# STM32F103RC.net
KiCad netlist of a schematic drawn in Altium Designer
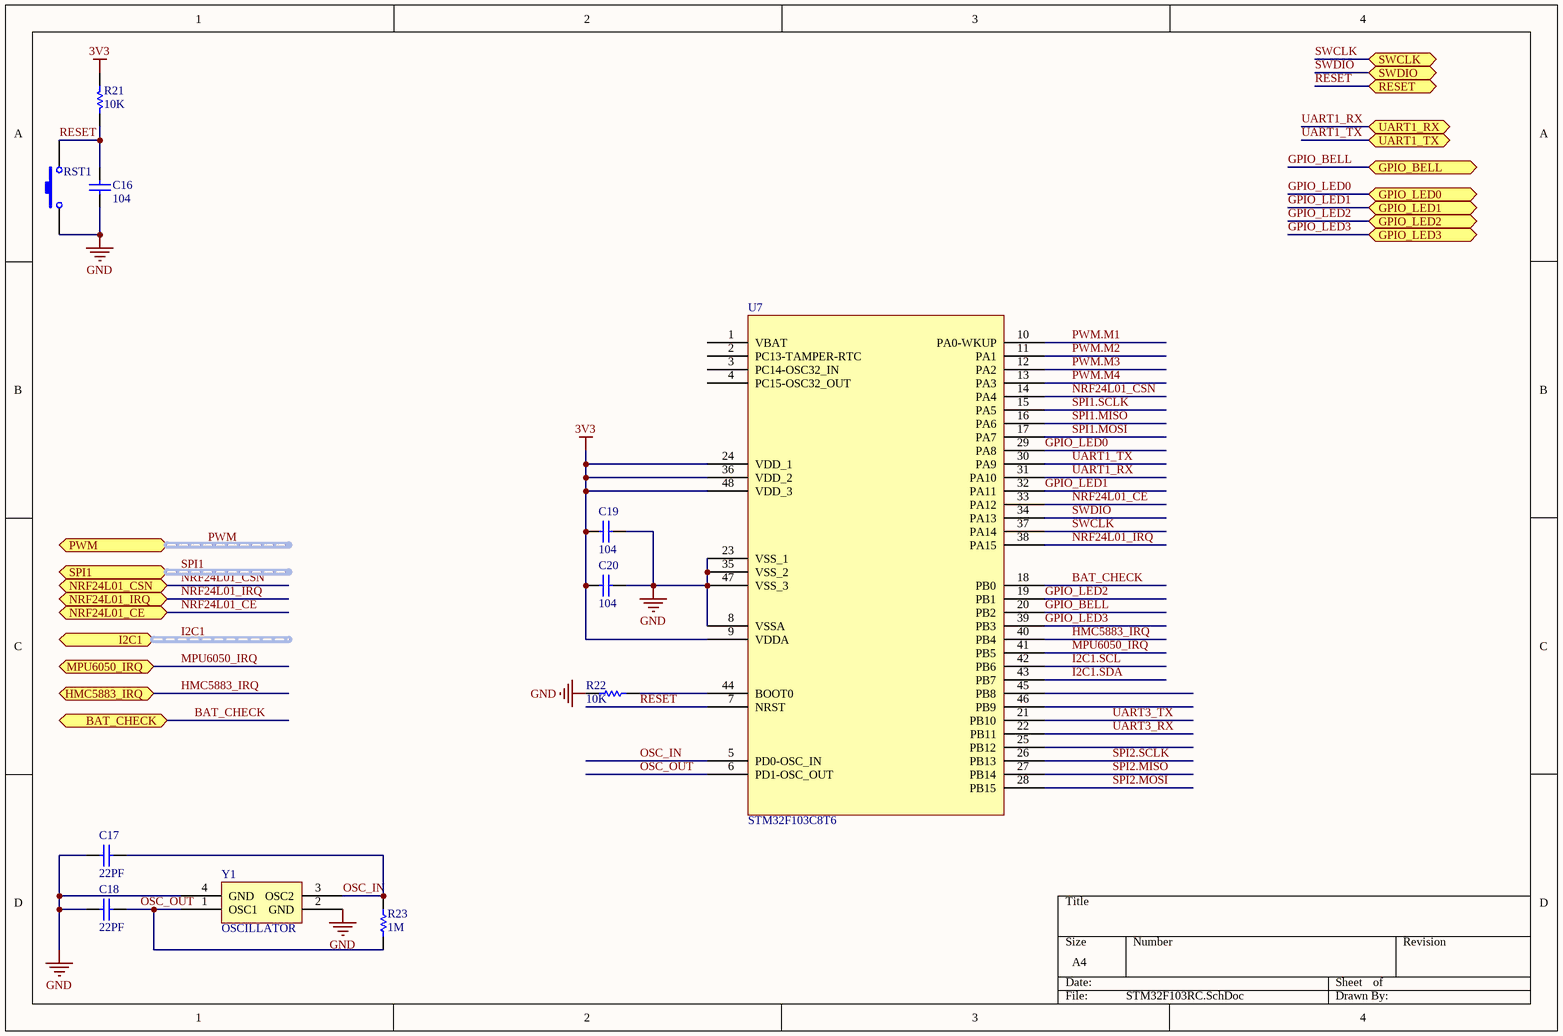
[diagram p0: STM32F103RC.SchDoc]

(export (version "E")
  (design (tool "Eeschema 10.0.6"))
  (components
    (comp (ref "C16")
      (value "104")
      (footprint "CAP_0603")
      (description "Capacitor")
      (fields (field (name "Comment") "Cap") (field (name "PUBLISHER") "Altium Limited"))
      (libsource (lib "Miscellaneous Devices") (part "Cap"))
    )
    (comp (ref "C17")
      (value "22PF")
      (footprint "CAP_0603")
      (description "Capacitor")
      (fields (field (name "Comment") "Cap") (field (name "PUBLISHER") "Altium Limited"))
      (libsource (lib "Miscellaneous Devices") (part "Cap"))
    )
    (comp (ref "C18")
      (value "22PF")
      (footprint "CAP_0603")
      (description "Capacitor")
      (fields (field (name "Comment") "Cap") (field (name "PUBLISHER") "Altium Limited"))
      (libsource (lib "Miscellaneous Devices") (part "Cap"))
    )
    (comp (ref "C19")
      (value "104")
      (footprint "CAP_0603")
      (description "Capacitor")
      (fields (field (name "Comment") "Cap") (field (name "PUBLISHER") "Altium Limited"))
      (libsource (lib "Miscellaneous Devices") (part "Cap"))
    )
    (comp (ref "C20")
      (value "104")
      (footprint "CAP_0603")
      (description "Capacitor")
      (fields (field (name "Comment") "Cap") (field (name "PUBLISHER") "Altium Limited"))
      (libsource (lib "Miscellaneous Devices") (part "Cap"))
    )
    (comp (ref "R21")
      (value "10K")
      (footprint "RES_0603")
      (description "Resistor")
      (fields (field (name "Comment") "Res1") (field (name "PUBLISHER") "Altium Limited"))
      (libsource (lib "Miscellaneous Devices") (part "Res1"))
    )
    (comp (ref "R22")
      (value "10K")
      (footprint "RES_0603")
      (description "Resistor")
      (fields (field (name "Comment") "Res1") (field (name "PUBLISHER") "Altium Limited"))
      (libsource (lib "Miscellaneous Devices") (part "Res1"))
    )
    (comp (ref "R23")
      (value "1M")
      (footprint "RES_0603")
      (description "Resistor")
      (fields (field (name "Comment") "Res1") (field (name "PUBLISHER") "Altium Limited"))
      (libsource (lib "Miscellaneous Devices") (part "Res1"))
    )
    (comp (ref "RST1")
      (value "SW-PB")
      (footprint "KEY")
      (description "Switch")
      (fields (field (name "PUBLISHER") "Altium Limited"))
      (libsource (lib "Miscellaneous Devices") (part "SW-PB"))
    )
    (comp (ref "U7")
      (value "STM32F103C8T6")
      (footprint "TQFP_48")
      (libsource (lib "Schlib1") (part "STM32F103C8T6"))
    )
    (comp (ref "Y1") (value "OSCILLATOR") (footprint "3225") (libsource (lib "Schlib1") (part "OSCILLATOR")))
  )
  (nets
    (net (code "4") (name "/BAT_CHECK") (class "Default")
      (node (ref "U7") (pin "18") (pinfunction "PB0_18") (pintype "passive"))
    )
    (net (code "5") (name "/GPIO_BELL") (class "Default")
      (node (ref "U7") (pin "20") (pinfunction "PB2_20") (pintype "passive"))
    )
    (net (code "6") (name "/GPIO_LED0") (class "Default")
      (node (ref "U7") (pin "29") (pinfunction "PA8_29") (pintype "passive"))
    )
    (net (code "7") (name "/GPIO_LED1") (class "Default")
      (node (ref "U7") (pin "32") (pinfunction "PA11_32") (pintype "passive"))
    )
    (net (code "8") (name "/GPIO_LED2") (class "Default")
      (node (ref "U7") (pin "19") (pinfunction "PB1_19") (pintype "passive"))
    )
    (net (code "9") (name "/GPIO_LED3") (class "Default")
      (node (ref "U7") (pin "39") (pinfunction "PB3_39") (pintype "passive"))
    )
    (net (code "10") (name "/HMC5883_IRQ") (class "Default")
      (node (ref "U7") (pin "40") (pinfunction "PB4_40") (pintype "passive"))
    )
    (net (code "11") (name "/I2C1.SCL") (class "Default")
      (node (ref "U7") (pin "42") (pinfunction "PB6_42") (pintype "passive"))
    )
    (net (code "12") (name "/I2C1.SDA") (class "Default")
      (node (ref "U7") (pin "43") (pinfunction "PB7_43") (pintype "passive"))
    )
    (net (code "13") (name "/MPU6050_IRQ") (class "Default")
      (node (ref "U7") (pin "41") (pinfunction "PB5_41") (pintype "passive"))
    )
    (net (code "14") (name "/NRF24L01_CE") (class "Default")
      (node (ref "U7") (pin "33") (pinfunction "PA12_33") (pintype "passive"))
    )
    (net (code "15") (name "/NRF24L01_CSN") (class "Default")
      (node (ref "U7") (pin "14") (pinfunction "PA4_14") (pintype "passive"))
    )
    (net (code "16") (name "/NRF24L01_IRQ") (class "Default")
      (node (ref "U7") (pin "38") (pinfunction "PA15_38") (pintype "passive"))
    )
    (net (code "17") (name "/OSC_IN") (class "Default")
      (node (ref "C17") (pin "2") (pinfunction "2_2") (pintype "passive"))
      (node (ref "R23") (pin "2") (pinfunction "2_2") (pintype "passive"))
      (node (ref "U7") (pin "5") (pinfunction "PD0-OSC_IN_5") (pintype "passive"))
      (node (ref "Y1") (pin "3") (pinfunction "OSC2_3") (pintype "passive"))
    )
    (net (code "18") (name "/OSC_OUT") (class "Default")
      (node (ref "C18") (pin "2") (pinfunction "2_2") (pintype "passive"))
      (node (ref "R23") (pin "1") (pinfunction "1_1") (pintype "passive"))
      (node (ref "U7") (pin "6") (pinfunction "PD1-OSC_OUT_6") (pintype "passive"))
      (node (ref "Y1") (pin "1") (pinfunction "OSC1_1") (pintype "passive"))
    )
    (net (code "19") (name "/PWM.M1") (class "Default")
      (node (ref "U7") (pin "10") (pinfunction "PA0-WKUP_10") (pintype "passive"))
    )
    (net (code "20") (name "/PWM.M2") (class "Default")
      (node (ref "U7") (pin "11") (pinfunction "PA1_11") (pintype "passive"))
    )
    (net (code "21") (name "/PWM.M3") (class "Default")
      (node (ref "U7") (pin "12") (pinfunction "PA2_12") (pintype "passive"))
    )
    (net (code "22") (name "/PWM.M4") (class "Default")
      (node (ref "U7") (pin "13") (pinfunction "PA3_13") (pintype "passive"))
    )
    (net (code "23") (name "/RESET") (class "Default")
      (node (ref "C16") (pin "1") (pinfunction "1_1") (pintype "passive"))
      (node (ref "R21") (pin "1") (pinfunction "1_1") (pintype "passive"))
      (node (ref "RST1") (pin "1") (pinfunction "1_1") (pintype "passive"))
      (node (ref "U7") (pin "7") (pinfunction "NRST_7") (pintype "passive"))
    )
    (net (code "24") (name "/SPI1.MISO") (class "Default")
      (node (ref "U7") (pin "16") (pinfunction "PA6_16") (pintype "passive"))
    )
    (net (code "25") (name "/SPI1.MOSI") (class "Default")
      (node (ref "U7") (pin "17") (pinfunction "PA7_17") (pintype "passive"))
    )
    (net (code "26") (name "/SPI1.SCLK") (class "Default")
      (node (ref "U7") (pin "15") (pinfunction "PA5_15") (pintype "passive"))
    )
    (net (code "27") (name "/SPI2.MISO") (class "Default")
      (node (ref "U7") (pin "27") (pinfunction "PB14_27") (pintype "passive"))
    )
    (net (code "28") (name "/SPI2.MOSI") (class "Default")
      (node (ref "U7") (pin "28") (pinfunction "PB15_28") (pintype "passive"))
    )
    (net (code "29") (name "/SPI2.SCLK") (class "Default")
      (node (ref "U7") (pin "26") (pinfunction "PB13_26") (pintype "passive"))
    )
    (net (code "30") (name "/SWCLK") (class "Default")
      (node (ref "U7") (pin "37") (pinfunction "PA14_37") (pintype "passive"))
    )
    (net (code "31") (name "/SWDIO") (class "Default")
      (node (ref "U7") (pin "34") (pinfunction "PA13_34") (pintype "passive"))
    )
    (net (code "32") (name "/UART1_RX") (class "Default")
      (node (ref "U7") (pin "31") (pinfunction "PA10_31") (pintype "passive"))
    )
    (net (code "33") (name "/UART1_TX") (class "Default")
      (node (ref "U7") (pin "30") (pinfunction "PA9_30") (pintype "passive"))
    )
    (net (code "34") (name "/UART3_RX") (class "Default")
      (node (ref "U7") (pin "22") (pinfunction "PB11_22") (pintype "passive"))
    )
    (net (code "35") (name "/UART3_TX") (class "Default")
      (node (ref "U7") (pin "21") (pinfunction "PB10_21") (pintype "passive"))
    )
    (net (code "39") (name "3V3") (class "Default")
      (node (ref "C19") (pin "1") (pinfunction "1_1") (pintype "passive"))
      (node (ref "C20") (pin "1") (pinfunction "1_1") (pintype "passive"))
      (node (ref "R21") (pin "2") (pinfunction "2_2") (pintype "passive"))
      (node (ref "U7") (pin "24") (pinfunction "VDD_1_24") (pintype "passive"))
      (node (ref "U7") (pin "36") (pinfunction "VDD_2_36") (pintype "passive"))
      (node (ref "U7") (pin "48") (pinfunction "VDD_3_48") (pintype "passive"))
      (node (ref "U7") (pin "9") (pinfunction "VDDA_9") (pintype "passive"))
    )
    (net (code "40") (name "GND") (class "Default")
      (node (ref "C16") (pin "2") (pinfunction "2_2") (pintype "passive"))
      (node (ref "C17") (pin "1") (pinfunction "1_1") (pintype "passive"))
      (node (ref "C18") (pin "1") (pinfunction "1_1") (pintype "passive"))
      (node (ref "C19") (pin "2") (pinfunction "2_2") (pintype "passive"))
      (node (ref "C20") (pin "2") (pinfunction "2_2") (pintype "passive"))
      (node (ref "R22") (pin "1") (pinfunction "1_1") (pintype "passive"))
      (node (ref "RST1") (pin "2") (pinfunction "2_2") (pintype "passive"))
      (node (ref "U7") (pin "23") (pinfunction "VSS_1_23") (pintype "passive"))
      (node (ref "U7") (pin "35") (pinfunction "VSS_2_35") (pintype "passive"))
      (node (ref "U7") (pin "47") (pinfunction "VSS_3_47") (pintype "passive"))
      (node (ref "U7") (pin "8") (pinfunction "VSSA_8") (pintype "passive"))
      (node (ref "Y1") (pin "2") (pinfunction "GND_2") (pintype "passive"))
      (node (ref "Y1") (pin "4") (pinfunction "GND_4") (pintype "passive"))
    )
    (net (code "41") (name "Net-(U7-BOOT0)") (class "Default")
      (node (ref "R22") (pin "2") (pinfunction "2_2") (pintype "passive"))
      (node (ref "U7") (pin "44") (pinfunction "BOOT0_44") (pintype "passive"))
    )
    (net (code "42") (name "unconnected-(U7-PB8-Pad45)") (class "Default")
      (node (ref "U7") (pin "45") (pinfunction "PB8_45") (pintype "passive"))
    )
    (net (code "43") (name "unconnected-(U7-PB9-Pad46)") (class "Default")
      (node (ref "U7") (pin "46") (pinfunction "PB9_46") (pintype "passive"))
    )
    (net (code "44") (name "unconnected-(U7-PB12-Pad25)") (class "Default")
      (node (ref "U7") (pin "25") (pinfunction "PB12_25") (pintype "passive"))
    )
    (net (code "45") (name "unconnected-(U7-PC13-TAMPER-RTC-Pad2)") (class "Default")
      (node (ref "U7") (pin "2") (pinfunction "PC13-TAMPER-RTC_2") (pintype "passive"))
    )
    (net (code "46") (name "unconnected-(U7-PC14-OSC32_IN-Pad3)") (class "Default")
      (node (ref "U7") (pin "3") (pinfunction "PC14-OSC32_IN_3") (pintype "passive"))
    )
    (net (code "47") (name "unconnected-(U7-PC15-OSC32_OUT-Pad4)") (class "Default")
      (node (ref "U7") (pin "4") (pinfunction "PC15-OSC32_OUT_4") (pintype "passive"))
    )
    (net (code "48") (name "unconnected-(U7-VBAT-Pad1)") (class "Default")
      (node (ref "U7") (pin "1") (pinfunction "VBAT_1") (pintype "passive"))
    )
  )
)
